# Smart-home.net
KiCad netlist of a schematic drawn in EAGLE
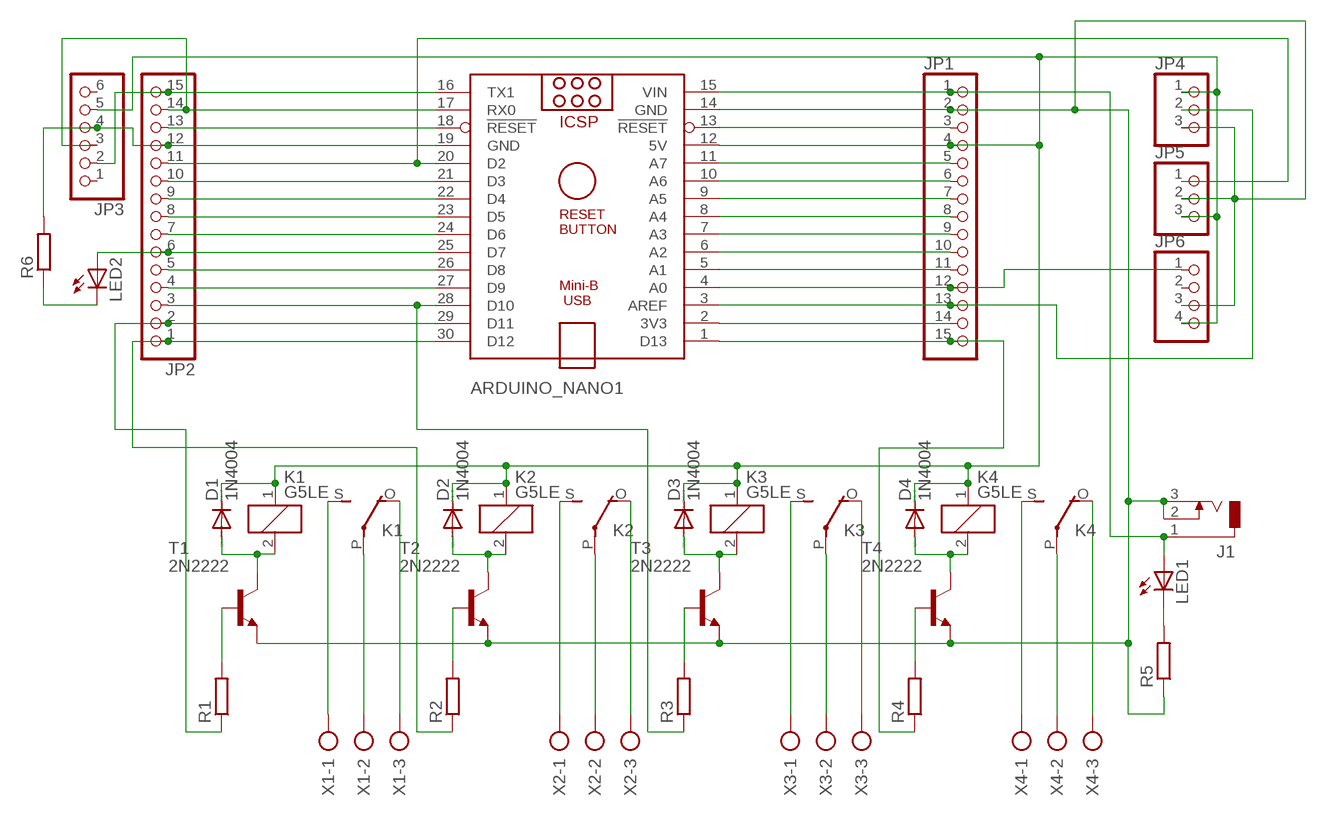
[diagram p0: schematic, sheet 1]

(export (version "E")
  (design (tool "Eeschema 10.0.6"))
  (components
    (comp (ref "ARDUINO_NANO1")
      (value "ARDUINO_NANO")
      (footprint "eagle-import:ARDUINO_NANO")
      (libsource (lib "eagle-import") (part "ARDUINO_NANO"))
    )
    (comp (ref "D1")
      (value "1N4004")
      (footprint "eagle-import:DO41-10")
      (libsource (lib "eagle-import") (part "1N4004"))
    )
    (comp (ref "D2")
      (value "1N4004")
      (footprint "eagle-import:DO41-10")
      (libsource (lib "eagle-import") (part "1N4004"))
    )
    (comp (ref "D3")
      (value "1N4004")
      (footprint "eagle-import:DO41-10")
      (libsource (lib "eagle-import") (part "1N4004"))
    )
    (comp (ref "D4")
      (value "1N4004")
      (footprint "eagle-import:DO41-10")
      (libsource (lib "eagle-import") (part "1N4004"))
    )
    (comp (ref "J1")
      (value "DCJ0303")
      (footprint "eagle-import:DCJ0303")
      (libsource (lib "eagle-import") (part "DCJ0303"))
    )
    (comp (ref "JP1")
      (value "PINHD-1X15")
      (footprint "eagle-import:1X15")
      (libsource (lib "eagle-import") (part "PINHD-1X15"))
    )
    (comp (ref "JP2")
      (value "PINHD-1X15")
      (footprint "eagle-import:1X15")
      (libsource (lib "eagle-import") (part "PINHD-1X15"))
    )
    (comp (ref "JP3")
      (value "PINHD-1X6")
      (footprint "eagle-import:1X06")
      (libsource (lib "eagle-import") (part "PINHD-1X6"))
    )
    (comp (ref "JP4")
      (value "PINHD-1X3")
      (footprint "eagle-import:1X03")
      (libsource (lib "eagle-import") (part "PINHD-1X3"))
    )
    (comp (ref "JP5")
      (value "PINHD-1X3")
      (footprint "eagle-import:1X03")
      (libsource (lib "eagle-import") (part "PINHD-1X3"))
    )
    (comp (ref "JP6")
      (value "PINHD-1X4")
      (footprint "eagle-import:1X04")
      (libsource (lib "eagle-import") (part "PINHD-1X4"))
    )
    (comp (ref "K1")
      (value "G5LE")
      (footprint "eagle-import:G5LE")
      (libsource (lib "eagle-import") (part "G5LE"))
    )
    (comp (ref "K2")
      (value "G5LE")
      (footprint "eagle-import:G5LE")
      (libsource (lib "eagle-import") (part "G5LE"))
    )
    (comp (ref "K3")
      (value "G5LE")
      (footprint "eagle-import:G5LE")
      (libsource (lib "eagle-import") (part "G5LE"))
    )
    (comp (ref "K4")
      (value "G5LE")
      (footprint "eagle-import:G5LE")
      (libsource (lib "eagle-import") (part "G5LE"))
    )
    (comp (ref "LED1")
      (value "LED3MM")
      (footprint "eagle-import:LED3MM")
      (libsource (lib "eagle-import") (part "LED3MM"))
    )
    (comp (ref "LED2")
      (value "LED3MM")
      (footprint "eagle-import:LED3MM")
      (libsource (lib "eagle-import") (part "LED3MM"))
    )
    (comp (ref "R1")
      (value "R-EU_0204/7")
      (footprint "eagle-import:0204_7")
      (libsource (lib "eagle-import") (part "R-EU_0204/7"))
    )
    (comp (ref "R2")
      (value "R-EU_0204/7")
      (footprint "eagle-import:0204_7")
      (libsource (lib "eagle-import") (part "R-EU_0204/7"))
    )
    (comp (ref "R3")
      (value "R-EU_0204/7")
      (footprint "eagle-import:0204_7")
      (libsource (lib "eagle-import") (part "R-EU_0204/7"))
    )
    (comp (ref "R4")
      (value "R-EU_0204/7")
      (footprint "eagle-import:0204_7")
      (libsource (lib "eagle-import") (part "R-EU_0204/7"))
    )
    (comp (ref "R5")
      (value "R-EU_0204/7")
      (footprint "eagle-import:0204_7")
      (libsource (lib "eagle-import") (part "R-EU_0204/7"))
    )
    (comp (ref "R6")
      (value "R-EU_0204/7")
      (footprint "eagle-import:0204_7")
      (libsource (lib "eagle-import") (part "R-EU_0204/7"))
    )
    (comp (ref "T1")
      (value "2N2222")
      (footprint "eagle-import:TO18")
      (libsource (lib "eagle-import") (part "2N2222"))
    )
    (comp (ref "T2")
      (value "2N2222")
      (footprint "eagle-import:TO18")
      (libsource (lib "eagle-import") (part "2N2222"))
    )
    (comp (ref "T3")
      (value "2N2222")
      (footprint "eagle-import:TO18")
      (libsource (lib "eagle-import") (part "2N2222"))
    )
    (comp (ref "T4")
      (value "2N2222")
      (footprint "eagle-import:TO18")
      (libsource (lib "eagle-import") (part "2N2222"))
    )
    (comp (ref "X1")
      (value "AK300/3")
      (footprint "eagle-import:AK300_3")
      (libsource (lib "eagle-import") (part "AK300/3"))
    )
    (comp (ref "X2")
      (value "AK300/3")
      (footprint "eagle-import:AK300_3")
      (libsource (lib "eagle-import") (part "AK300/3"))
    )
    (comp (ref "X3")
      (value "AK300/3")
      (footprint "eagle-import:AK300_3")
      (libsource (lib "eagle-import") (part "AK300/3"))
    )
    (comp (ref "X4")
      (value "AK300/3")
      (footprint "eagle-import:AK300_3")
      (libsource (lib "eagle-import") (part "AK300/3"))
    )
  )
  (nets
    (net (code "1") (name "Net-(ARDUINO_NANO1-3V3)") (class "Default")
      (node (ref "ARDUINO_NANO1") (pin "2") (pinfunction "3V3_2") (pintype "output"))
      (node (ref "JP1") (pin "14") (pinfunction "14_14") (pintype "passive"))
    )
    (net (code "2") (name "Net-(ARDUINO_NANO1-5V)") (class "Default")
      (node (ref "ARDUINO_NANO1") (pin "12") (pinfunction "5V_12") (pintype "power_in"))
      (node (ref "D1") (pin "C") (pinfunction "C_C") (pintype "passive"))
      (node (ref "D2") (pin "C") (pinfunction "C_C") (pintype "passive"))
      (node (ref "D3") (pin "C") (pinfunction "C_C") (pintype "passive"))
      (node (ref "D4") (pin "C") (pinfunction "C_C") (pintype "passive"))
      (node (ref "JP1") (pin "4") (pinfunction "4_4") (pintype "passive"))
      (node (ref "JP3") (pin "5") (pinfunction "5_5") (pintype "passive"))
      (node (ref "JP4") (pin "1") (pinfunction "1_1") (pintype "passive"))
      (node (ref "JP5") (pin "3") (pinfunction "3_3") (pintype "passive"))
      (node (ref "JP6") (pin "4") (pinfunction "4_4") (pintype "passive"))
      (node (ref "K1") (pin "1") (pinfunction "1_1") (pintype "passive"))
      (node (ref "K2") (pin "1") (pinfunction "1_1") (pintype "passive"))
      (node (ref "K3") (pin "1") (pinfunction "1_1") (pintype "passive"))
      (node (ref "K4") (pin "1") (pinfunction "1_1") (pintype "passive"))
    )
    (net (code "3") (name "Net-(ARDUINO_NANO1-A0)") (class "Default")
      (node (ref "ARDUINO_NANO1") (pin "4") (pinfunction "A0_4") (pintype "bidirectional"))
      (node (ref "JP1") (pin "12") (pinfunction "12_12") (pintype "passive"))
      (node (ref "JP6") (pin "1") (pinfunction "1_1") (pintype "passive"))
    )
    (net (code "4") (name "Net-(ARDUINO_NANO1-A1)") (class "Default")
      (node (ref "ARDUINO_NANO1") (pin "5") (pinfunction "A1_5") (pintype "bidirectional"))
      (node (ref "JP1") (pin "11") (pinfunction "11_11") (pintype "passive"))
    )
    (net (code "5") (name "Net-(ARDUINO_NANO1-A2)") (class "Default")
      (node (ref "ARDUINO_NANO1") (pin "6") (pinfunction "A2_6") (pintype "bidirectional"))
      (node (ref "JP1") (pin "10") (pinfunction "10_10") (pintype "passive"))
    )
    (net (code "6") (name "Net-(ARDUINO_NANO1-A3)") (class "Default")
      (node (ref "ARDUINO_NANO1") (pin "7") (pinfunction "A3_7") (pintype "bidirectional"))
      (node (ref "JP1") (pin "9") (pinfunction "9_9") (pintype "passive"))
    )
    (net (code "7") (name "Net-(ARDUINO_NANO1-A4)") (class "Default")
      (node (ref "ARDUINO_NANO1") (pin "8") (pinfunction "A4_8") (pintype "bidirectional"))
      (node (ref "JP1") (pin "8") (pinfunction "8_8") (pintype "passive"))
    )
    (net (code "8") (name "Net-(ARDUINO_NANO1-A5)") (class "Default")
      (node (ref "ARDUINO_NANO1") (pin "9") (pinfunction "A5_9") (pintype "bidirectional"))
      (node (ref "JP1") (pin "7") (pinfunction "7_7") (pintype "passive"))
    )
    (net (code "9") (name "Net-(ARDUINO_NANO1-A6)") (class "Default")
      (node (ref "ARDUINO_NANO1") (pin "10") (pinfunction "A6_10") (pintype "bidirectional"))
      (node (ref "JP1") (pin "6") (pinfunction "6_6") (pintype "passive"))
    )
    (net (code "10") (name "Net-(ARDUINO_NANO1-A7)") (class "Default")
      (node (ref "ARDUINO_NANO1") (pin "11") (pinfunction "A7_11") (pintype "bidirectional"))
      (node (ref "JP1") (pin "5") (pinfunction "5_5") (pintype "passive"))
    )
    (net (code "11") (name "Net-(ARDUINO_NANO1-AREF)") (class "Default")
      (node (ref "ARDUINO_NANO1") (pin "3") (pinfunction "AREF_3") (pintype "input"))
      (node (ref "JP1") (pin "13") (pinfunction "13_13") (pintype "passive"))
      (node (ref "JP4") (pin "2") (pinfunction "2_2") (pintype "passive"))
    )
    (net (code "12") (name "Net-(ARDUINO_NANO1-D2)") (class "Default")
      (node (ref "ARDUINO_NANO1") (pin "20") (pinfunction "D2_20") (pintype "bidirectional"))
      (node (ref "JP2") (pin "11") (pinfunction "11_11") (pintype "passive"))
      (node (ref "JP5") (pin "1") (pinfunction "1_1") (pintype "passive"))
    )
    (net (code "13") (name "Net-(ARDUINO_NANO1-D3)") (class "Default")
      (node (ref "ARDUINO_NANO1") (pin "21") (pinfunction "D3_21") (pintype "bidirectional"))
      (node (ref "JP2") (pin "10") (pinfunction "10_10") (pintype "passive"))
    )
    (net (code "14") (name "Net-(ARDUINO_NANO1-D4)") (class "Default")
      (node (ref "ARDUINO_NANO1") (pin "22") (pinfunction "D4_22") (pintype "bidirectional"))
      (node (ref "JP2") (pin "9") (pinfunction "9_9") (pintype "passive"))
    )
    (net (code "15") (name "Net-(ARDUINO_NANO1-D5)") (class "Default")
      (node (ref "ARDUINO_NANO1") (pin "23") (pinfunction "D5_23") (pintype "bidirectional"))
      (node (ref "JP2") (pin "8") (pinfunction "8_8") (pintype "passive"))
    )
    (net (code "16") (name "Net-(ARDUINO_NANO1-D6)") (class "Default")
      (node (ref "ARDUINO_NANO1") (pin "24") (pinfunction "D6_24") (pintype "bidirectional"))
      (node (ref "JP2") (pin "7") (pinfunction "7_7") (pintype "passive"))
    )
    (net (code "17") (name "Net-(ARDUINO_NANO1-D7)") (class "Default")
      (node (ref "ARDUINO_NANO1") (pin "25") (pinfunction "D7_25") (pintype "bidirectional"))
      (node (ref "JP2") (pin "6") (pinfunction "6_6") (pintype "passive"))
      (node (ref "LED2") (pin "A") (pinfunction "A_A") (pintype "passive"))
    )
    (net (code "18") (name "Net-(ARDUINO_NANO1-D8)") (class "Default")
      (node (ref "ARDUINO_NANO1") (pin "26") (pinfunction "D8_26") (pintype "bidirectional"))
      (node (ref "JP2") (pin "5") (pinfunction "5_5") (pintype "passive"))
    )
    (net (code "19") (name "Net-(ARDUINO_NANO1-D9)") (class "Default")
      (node (ref "ARDUINO_NANO1") (pin "27") (pinfunction "D9_27") (pintype "bidirectional"))
      (node (ref "JP2") (pin "4") (pinfunction "4_4") (pintype "passive"))
    )
    (net (code "20") (name "Net-(ARDUINO_NANO1-D10)") (class "Default")
      (node (ref "ARDUINO_NANO1") (pin "28") (pinfunction "D10_28") (pintype "bidirectional"))
      (node (ref "JP2") (pin "3") (pinfunction "3_3") (pintype "passive"))
      (node (ref "R3") (pin "1") (pinfunction "1_1") (pintype "passive"))
    )
    (net (code "21") (name "Net-(ARDUINO_NANO1-D11)") (class "Default")
      (node (ref "ARDUINO_NANO1") (pin "29") (pinfunction "D11_29") (pintype "bidirectional"))
      (node (ref "JP2") (pin "2") (pinfunction "2_2") (pintype "passive"))
      (node (ref "R1") (pin "1") (pinfunction "1_1") (pintype "passive"))
    )
    (net (code "22") (name "Net-(ARDUINO_NANO1-D12)") (class "Default")
      (node (ref "ARDUINO_NANO1") (pin "30") (pinfunction "D12_30") (pintype "bidirectional"))
      (node (ref "JP2") (pin "1") (pinfunction "1_1") (pintype "passive"))
      (node (ref "R2") (pin "1") (pinfunction "1_1") (pintype "passive"))
    )
    (net (code "23") (name "Net-(ARDUINO_NANO1-D13)") (class "Default")
      (node (ref "ARDUINO_NANO1") (pin "1") (pinfunction "D13_1") (pintype "bidirectional"))
      (node (ref "JP1") (pin "15") (pinfunction "15_15") (pintype "passive"))
      (node (ref "R4") (pin "1") (pinfunction "1_1") (pintype "passive"))
    )
    (net (code "24") (name "Net-(ARDUINO_NANO1-GND-Pad19)") (class "Default")
      (node (ref "ARDUINO_NANO1") (pin "19") (pinfunction "GND_19") (pintype "power_in"))
      (node (ref "JP2") (pin "12") (pinfunction "12_12") (pintype "passive"))
      (node (ref "JP3") (pin "4") (pinfunction "4_4") (pintype "passive"))
      (node (ref "R6") (pin "2") (pinfunction "2_2") (pintype "passive"))
    )
    (net (code "25") (name "Net-(ARDUINO_NANO1-RX0)") (class "Default")
      (node (ref "ARDUINO_NANO1") (pin "17") (pinfunction "RX0_17") (pintype "bidirectional"))
      (node (ref "JP2") (pin "14") (pinfunction "14_14") (pintype "passive"))
      (node (ref "JP3") (pin "3") (pinfunction "3_3") (pintype "passive"))
    )
    (net (code "26") (name "Net-(ARDUINO_NANO1-TX1)") (class "Default")
      (node (ref "ARDUINO_NANO1") (pin "16") (pinfunction "TX1_16") (pintype "bidirectional"))
      (node (ref "JP2") (pin "15") (pinfunction "15_15") (pintype "passive"))
      (node (ref "JP3") (pin "2") (pinfunction "2_2") (pintype "passive"))
    )
    (net (code "27") (name "Net-(ARDUINO_NANO1-VIN)") (class "Default")
      (node (ref "ARDUINO_NANO1") (pin "15") (pinfunction "VIN_15") (pintype "power_in"))
      (node (ref "J1") (pin "1") (pinfunction "1_1") (pintype "passive"))
      (node (ref "JP1") (pin "1") (pinfunction "1_1") (pintype "passive"))
      (node (ref "LED1") (pin "A") (pinfunction "A_A") (pintype "passive"))
    )
    (net (code "28") (name "Net-(ARDUINO_NANO1-~{RESET}-Pad13)") (class "Default")
      (node (ref "ARDUINO_NANO1") (pin "13") (pinfunction "~{RESET}_13") (pintype "input"))
      (node (ref "JP1") (pin "3") (pinfunction "3_3") (pintype "passive"))
    )
    (net (code "29") (name "Net-(ARDUINO_NANO1-~{RESET}-Pad18)") (class "Default")
      (node (ref "ARDUINO_NANO1") (pin "18") (pinfunction "~{RESET}_18") (pintype "input"))
      (node (ref "JP2") (pin "13") (pinfunction "13_13") (pintype "passive"))
    )
    (net (code "30") (name "Net-(LED1-C)") (class "Default")
      (node (ref "LED1") (pin "K") (pinfunction "C_K") (pintype "passive"))
      (node (ref "R5") (pin "2") (pinfunction "2_2") (pintype "passive"))
    )
    (net (code "31") (name "Net-(LED2-C)") (class "Default")
      (node (ref "LED2") (pin "K") (pinfunction "C_K") (pintype "passive"))
      (node (ref "R6") (pin "1") (pinfunction "1_1") (pintype "passive"))
    )
    (net (code "32") (name "Net-(T1-B)") (class "Default")
      (node (ref "R1") (pin "2") (pinfunction "2_2") (pintype "passive"))
      (node (ref "T1") (pin "2") (pinfunction "B_2") (pintype "passive"))
    )
    (net (code "33") (name "Net-(T1-C)") (class "Default")
      (node (ref "D1") (pin "A") (pinfunction "A_A") (pintype "passive"))
      (node (ref "K1") (pin "2") (pinfunction "2_2") (pintype "passive"))
      (node (ref "T1") (pin "3") (pinfunction "C_3") (pintype "passive"))
    )
    (net (code "34") (name "Net-(T1-E)") (class "Default")
      (node (ref "ARDUINO_NANO1") (pin "14") (pinfunction "GND_14") (pintype "power_in"))
      (node (ref "J1") (pin "2") (pinfunction "2_2") (pintype "passive"))
      (node (ref "J1") (pin "3") (pinfunction "3_3") (pintype "passive"))
      (node (ref "JP1") (pin "2") (pinfunction "2_2") (pintype "passive"))
      (node (ref "JP4") (pin "3") (pinfunction "3_3") (pintype "passive"))
      (node (ref "JP5") (pin "2") (pinfunction "2_2") (pintype "passive"))
      (node (ref "JP6") (pin "3") (pinfunction "3_3") (pintype "passive"))
      (node (ref "R5") (pin "1") (pinfunction "1_1") (pintype "passive"))
      (node (ref "T1") (pin "1") (pinfunction "E_1") (pintype "passive"))
      (node (ref "T2") (pin "1") (pinfunction "E_1") (pintype "passive"))
      (node (ref "T3") (pin "1") (pinfunction "E_1") (pintype "passive"))
      (node (ref "T4") (pin "1") (pinfunction "E_1") (pintype "passive"))
    )
    (net (code "35") (name "Net-(T2-B)") (class "Default")
      (node (ref "R2") (pin "2") (pinfunction "2_2") (pintype "passive"))
      (node (ref "T2") (pin "2") (pinfunction "B_2") (pintype "passive"))
    )
    (net (code "36") (name "Net-(T2-C)") (class "Default")
      (node (ref "D2") (pin "A") (pinfunction "A_A") (pintype "passive"))
      (node (ref "K2") (pin "2") (pinfunction "2_2") (pintype "passive"))
      (node (ref "T2") (pin "3") (pinfunction "C_3") (pintype "passive"))
    )
    (net (code "37") (name "Net-(T3-B)") (class "Default")
      (node (ref "R3") (pin "2") (pinfunction "2_2") (pintype "passive"))
      (node (ref "T3") (pin "2") (pinfunction "B_2") (pintype "passive"))
    )
    (net (code "38") (name "Net-(T3-C)") (class "Default")
      (node (ref "D3") (pin "A") (pinfunction "A_A") (pintype "passive"))
      (node (ref "K3") (pin "2") (pinfunction "2_2") (pintype "passive"))
      (node (ref "T3") (pin "3") (pinfunction "C_3") (pintype "passive"))
    )
    (net (code "39") (name "Net-(T4-B)") (class "Default")
      (node (ref "R4") (pin "2") (pinfunction "2_2") (pintype "passive"))
      (node (ref "T4") (pin "2") (pinfunction "B_2") (pintype "passive"))
    )
    (net (code "40") (name "Net-(T4-C)") (class "Default")
      (node (ref "D4") (pin "A") (pinfunction "A_A") (pintype "passive"))
      (node (ref "K4") (pin "2") (pinfunction "2_2") (pintype "passive"))
      (node (ref "T4") (pin "3") (pinfunction "C_3") (pintype "passive"))
    )
    (net (code "41") (name "Net-(X1A-KL)") (class "Default")
      (node (ref "K1") (pin "S") (pinfunction "S_S") (pintype "passive"))
      (node (ref "X1") (pin "1") (pinfunction "KL_1") (pintype "passive"))
    )
    (net (code "42") (name "Net-(X1B-KL)") (class "Default")
      (node (ref "K1") (pin "P") (pinfunction "P_P") (pintype "passive"))
      (node (ref "X1") (pin "2") (pinfunction "KL_2") (pintype "passive"))
    )
    (net (code "43") (name "Net-(X1C-KL)") (class "Default")
      (node (ref "K1") (pin "O") (pinfunction "O_O") (pintype "passive"))
      (node (ref "X1") (pin "3") (pinfunction "KL_3") (pintype "passive"))
    )
    (net (code "44") (name "Net-(X2A-KL)") (class "Default")
      (node (ref "K2") (pin "S") (pinfunction "S_S") (pintype "passive"))
      (node (ref "X2") (pin "1") (pinfunction "KL_1") (pintype "passive"))
    )
    (net (code "45") (name "Net-(X2B-KL)") (class "Default")
      (node (ref "K2") (pin "P") (pinfunction "P_P") (pintype "passive"))
      (node (ref "X2") (pin "2") (pinfunction "KL_2") (pintype "passive"))
    )
    (net (code "46") (name "Net-(X2C-KL)") (class "Default")
      (node (ref "K2") (pin "O") (pinfunction "O_O") (pintype "passive"))
      (node (ref "X2") (pin "3") (pinfunction "KL_3") (pintype "passive"))
    )
    (net (code "47") (name "Net-(X3A-KL)") (class "Default")
      (node (ref "K3") (pin "S") (pinfunction "S_S") (pintype "passive"))
      (node (ref "X3") (pin "1") (pinfunction "KL_1") (pintype "passive"))
    )
    (net (code "48") (name "Net-(X3B-KL)") (class "Default")
      (node (ref "K3") (pin "P") (pinfunction "P_P") (pintype "passive"))
      (node (ref "X3") (pin "2") (pinfunction "KL_2") (pintype "passive"))
    )
    (net (code "49") (name "Net-(X3C-KL)") (class "Default")
      (node (ref "K3") (pin "O") (pinfunction "O_O") (pintype "passive"))
      (node (ref "X3") (pin "3") (pinfunction "KL_3") (pintype "passive"))
    )
    (net (code "50") (name "Net-(X4A-KL)") (class "Default")
      (node (ref "K4") (pin "S") (pinfunction "S_S") (pintype "passive"))
      (node (ref "X4") (pin "1") (pinfunction "KL_1") (pintype "passive"))
    )
    (net (code "51") (name "Net-(X4B-KL)") (class "Default")
      (node (ref "K4") (pin "P") (pinfunction "P_P") (pintype "passive"))
      (node (ref "X4") (pin "2") (pinfunction "KL_2") (pintype "passive"))
    )
    (net (code "52") (name "Net-(X4C-KL)") (class "Default")
      (node (ref "K4") (pin "O") (pinfunction "O_O") (pintype "passive"))
      (node (ref "X4") (pin "3") (pinfunction "KL_3") (pintype "passive"))
    )
    (net (code "53") (name "unconnected-(JP3-Pad1)") (class "Default")
      (node (ref "JP3") (pin "1") (pinfunction "1_1") (pintype "passive"))
    )
    (net (code "54") (name "unconnected-(JP3-Pad6)") (class "Default")
      (node (ref "JP3") (pin "6") (pinfunction "6_6") (pintype "passive"))
    )
    (net (code "55") (name "unconnected-(JP6-Pad2)") (class "Default")
      (node (ref "JP6") (pin "2") (pinfunction "2_2") (pintype "passive"))
    )
  )
)
